# KeySwitch.net
KiCad netlist of a schematic drawn in EAGLE
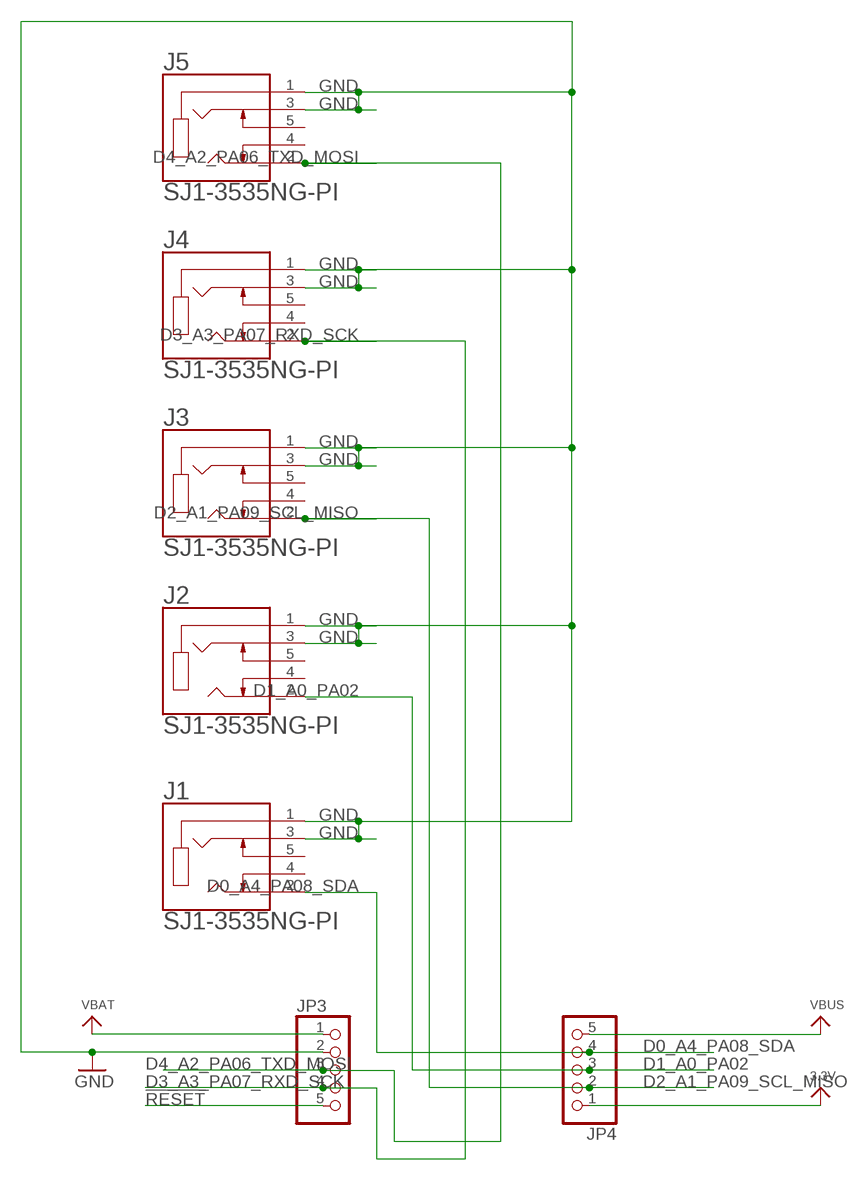
[diagram p0: schematic, sheet 1]

(export (version "E")
  (design (tool "Eeschema 10.0.6"))
  (components
    (comp (ref "J1")
      (value "SJ1-3535NG-PI")
      (footprint "eagle-import:CUI_SJ1-3535NG-PI")
      (fields (field (name "MANUFACTURER") "CUI"))
      (libsource (lib "eagle-import") (part "SJ1-3535NG-PI"))
    )
    (comp (ref "J2")
      (value "SJ1-3535NG-PI")
      (footprint "eagle-import:CUI_SJ1-3535NG-PI")
      (fields (field (name "MANUFACTURER") "CUI"))
      (libsource (lib "eagle-import") (part "SJ1-3535NG-PI"))
    )
    (comp (ref "J3")
      (value "SJ1-3535NG-PI")
      (footprint "eagle-import:CUI_SJ1-3535NG-PI")
      (fields (field (name "MANUFACTURER") "CUI"))
      (libsource (lib "eagle-import") (part "SJ1-3535NG-PI"))
    )
    (comp (ref "J4")
      (value "SJ1-3535NG-PI")
      (footprint "eagle-import:CUI_SJ1-3535NG-PI")
      (fields (field (name "MANUFACTURER") "CUI"))
      (libsource (lib "eagle-import") (part "SJ1-3535NG-PI"))
    )
    (comp (ref "J5")
      (value "SJ1-3535NG-PI")
      (footprint "eagle-import:CUI_SJ1-3535NG-PI")
      (fields (field (name "MANUFACTURER") "CUI"))
      (libsource (lib "eagle-import") (part "SJ1-3535NG-PI"))
    )
    (comp (ref "JP3")
      (value "HEADER-1X576MIL")
      (footprint "eagle-import:1X05_ROUND_76")
      (libsource (lib "eagle-import") (part "HEADER-1X576MIL"))
    )
    (comp (ref "JP4")
      (value "HEADER-1X576MIL")
      (footprint "eagle-import:1X05_ROUND_76")
      (libsource (lib "eagle-import") (part "HEADER-1X576MIL"))
    )
  )
  (nets
    (net (code "1") (name "/D0_A4_PA08_SDA") (class "Default")
      (node (ref "J1") (pin "2") (pinfunction "2_2") (pintype "passive"))
      (node (ref "JP4") (pin "4") (pinfunction "4_4") (pintype "passive"))
    )
    (net (code "2") (name "/D1_A0_PA02") (class "Default")
      (node (ref "J2") (pin "2") (pinfunction "2_2") (pintype "passive"))
      (node (ref "JP4") (pin "3") (pinfunction "3_3") (pintype "passive"))
    )
    (net (code "3") (name "/D2_A1_PA09_SCL_MISO") (class "Default")
      (node (ref "J3") (pin "2") (pinfunction "2_2") (pintype "passive"))
      (node (ref "JP4") (pin "2") (pinfunction "2_2") (pintype "passive"))
    )
    (net (code "4") (name "/D3_A3_PA07_RXD_SCK") (class "Default")
      (node (ref "J4") (pin "2") (pinfunction "2_2") (pintype "passive"))
      (node (ref "JP3") (pin "4") (pinfunction "4_4") (pintype "passive"))
    )
    (net (code "5") (name "/D4_A2_PA06_TXD_MOSI") (class "Default")
      (node (ref "J5") (pin "2") (pinfunction "2_2") (pintype "passive"))
      (node (ref "JP3") (pin "3") (pinfunction "3_3") (pintype "passive"))
    )
    (net (code "6") (name "/~{RESET}") (class "Default")
      (node (ref "JP3") (pin "5") (pinfunction "5_5") (pintype "passive"))
    )
    (net (code "7") (name "3.3V") (class "Default")
      (node (ref "JP4") (pin "1") (pinfunction "1_1") (pintype "passive"))
    )
    (net (code "8") (name "GND") (class "Default")
      (node (ref "J1") (pin "1") (pinfunction "1_1") (pintype "passive"))
      (node (ref "J1") (pin "3") (pinfunction "3_3") (pintype "passive"))
      (node (ref "J2") (pin "1") (pinfunction "1_1") (pintype "passive"))
      (node (ref "J2") (pin "3") (pinfunction "3_3") (pintype "passive"))
      (node (ref "J3") (pin "1") (pinfunction "1_1") (pintype "passive"))
      (node (ref "J3") (pin "3") (pinfunction "3_3") (pintype "passive"))
      (node (ref "J4") (pin "1") (pinfunction "1_1") (pintype "passive"))
      (node (ref "J4") (pin "3") (pinfunction "3_3") (pintype "passive"))
      (node (ref "J5") (pin "1") (pinfunction "1_1") (pintype "passive"))
      (node (ref "J5") (pin "3") (pinfunction "3_3") (pintype "passive"))
      (node (ref "JP3") (pin "2") (pinfunction "2_2") (pintype "passive"))
    )
    (net (code "9") (name "VBAT") (class "Default")
      (node (ref "JP3") (pin "1") (pinfunction "1_1") (pintype "passive"))
    )
    (net (code "10") (name "VBUS") (class "Default")
      (node (ref "JP4") (pin "5") (pinfunction "5_5") (pintype "passive"))
    )
    (net (code "11") (name "unconnected-(J1-Pad4)") (class "Default")
      (node (ref "J1") (pin "4") (pinfunction "4_4") (pintype "passive"))
    )
    (net (code "12") (name "unconnected-(J1-Pad5)") (class "Default")
      (node (ref "J1") (pin "5") (pinfunction "5_5") (pintype "passive"))
    )
    (net (code "13") (name "unconnected-(J2-Pad4)") (class "Default")
      (node (ref "J2") (pin "4") (pinfunction "4_4") (pintype "passive"))
    )
    (net (code "14") (name "unconnected-(J2-Pad5)") (class "Default")
      (node (ref "J2") (pin "5") (pinfunction "5_5") (pintype "passive"))
    )
    (net (code "15") (name "unconnected-(J3-Pad4)") (class "Default")
      (node (ref "J3") (pin "4") (pinfunction "4_4") (pintype "passive"))
    )
    (net (code "16") (name "unconnected-(J3-Pad5)") (class "Default")
      (node (ref "J3") (pin "5") (pinfunction "5_5") (pintype "passive"))
    )
    (net (code "17") (name "unconnected-(J4-Pad4)") (class "Default")
      (node (ref "J4") (pin "4") (pinfunction "4_4") (pintype "passive"))
    )
    (net (code "18") (name "unconnected-(J4-Pad5)") (class "Default")
      (node (ref "J4") (pin "5") (pinfunction "5_5") (pintype "passive"))
    )
    (net (code "19") (name "unconnected-(J5-Pad4)") (class "Default")
      (node (ref "J5") (pin "4") (pinfunction "4_4") (pintype "passive"))
    )
    (net (code "20") (name "unconnected-(J5-Pad5)") (class "Default")
      (node (ref "J5") (pin "5") (pinfunction "5_5") (pintype "passive"))
    )
  )
)
